# Balancer.net
KiCad netlist of a schematic drawn in EAGLE
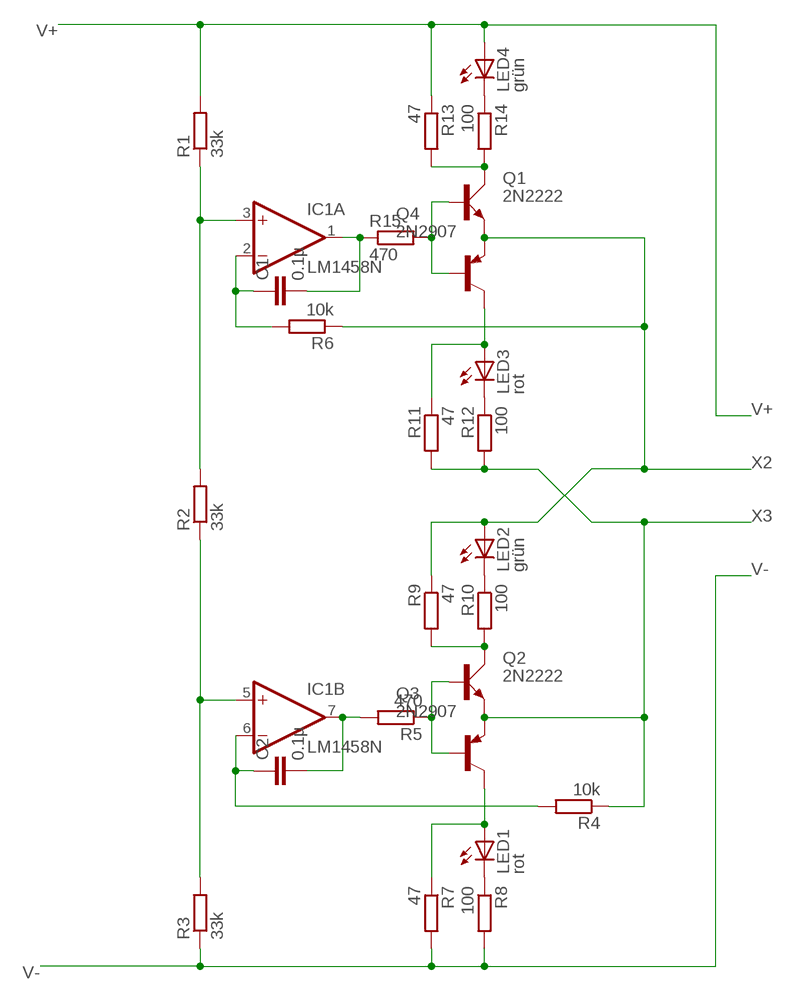
[diagram p0: schematic, sheet 1]

(export (version "E")
  (design (tool "Eeschema 10.0.6"))
  (components
    (comp (ref "C1")
      (value "0.1µ")
      (footprint "eagle-import:C050-025X075")
      (libsource (lib "eagle-import") (part "C-EU050-025X075"))
    )
    (comp (ref "C2")
      (value "0.1µ")
      (footprint "eagle-import:C050-025X075")
      (libsource (lib "eagle-import") (part "C-EU050-025X075"))
    )
    (comp (ref "IC1")
      (value "LM1458N")
      (footprint "eagle-import:DIL08")
      (libsource (lib "eagle-import") (part "1458NLM"))
    )
    (comp (ref "LED1")
      (value "rot")
      (footprint "eagle-import:LED5MM")
      (libsource (lib "eagle-import") (part "LED5MM"))
    )
    (comp (ref "LED2")
      (value "grün")
      (footprint "eagle-import:LED5MM")
      (libsource (lib "eagle-import") (part "LED5MM"))
    )
    (comp (ref "LED3")
      (value "rot")
      (footprint "eagle-import:LED5MM")
      (libsource (lib "eagle-import") (part "LED5MM"))
    )
    (comp (ref "LED4")
      (value "grün")
      (footprint "eagle-import:LED5MM")
      (libsource (lib "eagle-import") (part "LED5MM"))
    )
    (comp (ref "Q1")
      (value "2N2222")
      (footprint "eagle-import:TO18A")
      (libsource (lib "eagle-import") (part "2N2222"))
    )
    (comp (ref "Q2")
      (value "2N2222")
      (footprint "eagle-import:TO18A")
      (libsource (lib "eagle-import") (part "2N2222"))
    )
    (comp (ref "Q3")
      (value "2N2907")
      (footprint "eagle-import:TO18")
      (libsource (lib "eagle-import") (part "2N2907"))
    )
    (comp (ref "Q4")
      (value "2N2907")
      (footprint "eagle-import:TO18")
      (libsource (lib "eagle-import") (part "2N2907"))
    )
    (comp (ref "R1")
      (value "33k")
      (footprint "eagle-import:0204_5")
      (libsource (lib "eagle-import") (part "R-EU_0204/5"))
    )
    (comp (ref "R2")
      (value "33k")
      (footprint "eagle-import:0204_5")
      (libsource (lib "eagle-import") (part "R-EU_0204/5"))
    )
    (comp (ref "R3")
      (value "33k")
      (footprint "eagle-import:0204_5")
      (libsource (lib "eagle-import") (part "R-EU_0204/5"))
    )
    (comp (ref "R4")
      (value "10k")
      (footprint "eagle-import:0204_5")
      (libsource (lib "eagle-import") (part "R-EU_0204/5"))
    )
    (comp (ref "R5")
      (value "470")
      (footprint "eagle-import:0204_5")
      (libsource (lib "eagle-import") (part "R-EU_0204/5"))
    )
    (comp (ref "R6")
      (value "10k")
      (footprint "eagle-import:0204_5")
      (libsource (lib "eagle-import") (part "R-EU_0204/5"))
    )
    (comp (ref "R7")
      (value "47")
      (footprint "eagle-import:0204_5")
      (libsource (lib "eagle-import") (part "R-EU_0204/5"))
    )
    (comp (ref "R8")
      (value "100")
      (footprint "eagle-import:0204_5")
      (libsource (lib "eagle-import") (part "R-EU_0204/5"))
    )
    (comp (ref "R9")
      (value "47")
      (footprint "eagle-import:0204_5")
      (libsource (lib "eagle-import") (part "R-EU_0204/5"))
    )
    (comp (ref "R10")
      (value "100")
      (footprint "eagle-import:0204_5")
      (libsource (lib "eagle-import") (part "R-EU_0204/5"))
    )
    (comp (ref "R11")
      (value "47")
      (footprint "eagle-import:0204_5")
      (libsource (lib "eagle-import") (part "R-EU_0204/5"))
    )
    (comp (ref "R12")
      (value "100")
      (footprint "eagle-import:0204_5")
      (libsource (lib "eagle-import") (part "R-EU_0204/5"))
    )
    (comp (ref "R13")
      (value "47")
      (footprint "eagle-import:0204_5")
      (libsource (lib "eagle-import") (part "R-EU_0204/5"))
    )
    (comp (ref "R14")
      (value "100")
      (footprint "eagle-import:0204_5")
      (libsource (lib "eagle-import") (part "R-EU_0204/5"))
    )
    (comp (ref "R15")
      (value "470")
      (footprint "eagle-import:0204_5")
      (libsource (lib "eagle-import") (part "R-EU_0204/5"))
    )
  )
  (nets
    (net (code "1") (name "/V+") (class "Default")
      (node (ref "LED4") (pin "A") (pinfunction "A_A") (pintype "passive"))
      (node (ref "R1") (pin "2") (pinfunction "2_2") (pintype "passive"))
      (node (ref "R13") (pin "1") (pinfunction "1_1") (pintype "passive"))
    )
    (net (code "2") (name "/V-") (class "Default")
      (node (ref "R3") (pin "1") (pinfunction "1_1") (pintype "passive"))
      (node (ref "R7") (pin "2") (pinfunction "2_2") (pintype "passive"))
      (node (ref "R8") (pin "2") (pinfunction "2_2") (pintype "passive"))
    )
    (net (code "3") (name "/X2") (class "Default")
      (node (ref "LED2") (pin "A") (pinfunction "A_A") (pintype "passive"))
      (node (ref "Q1") (pin "E") (pinfunction "E_E") (pintype "passive"))
      (node (ref "Q4") (pin "1") (pinfunction "E_1") (pintype "passive"))
      (node (ref "R6") (pin "1") (pinfunction "1_1") (pintype "passive"))
      (node (ref "R9") (pin "1") (pinfunction "1_1") (pintype "passive"))
    )
    (net (code "4") (name "/X3") (class "Default")
      (node (ref "Q2") (pin "E") (pinfunction "E_E") (pintype "passive"))
      (node (ref "Q3") (pin "1") (pinfunction "E_1") (pintype "passive"))
      (node (ref "R11") (pin "2") (pinfunction "2_2") (pintype "passive"))
      (node (ref "R12") (pin "2") (pinfunction "2_2") (pintype "passive"))
      (node (ref "R4") (pin "1") (pinfunction "1_1") (pintype "passive"))
    )
    (net (code "5") (name "Net-(IC1A-+IN)") (class "Default")
      (node (ref "IC1") (pin "3") (pinfunction "+IN_3") (pintype "input"))
      (node (ref "R1") (pin "1") (pinfunction "1_1") (pintype "passive"))
      (node (ref "R2") (pin "2") (pinfunction "2_2") (pintype "passive"))
    )
    (net (code "6") (name "Net-(IC1A--IN)") (class "Default")
      (node (ref "C1") (pin "1") (pinfunction "1_1") (pintype "passive"))
      (node (ref "IC1") (pin "2") (pinfunction "-IN_2") (pintype "input"))
      (node (ref "R6") (pin "2") (pinfunction "2_2") (pintype "passive"))
    )
    (net (code "7") (name "Net-(IC1A-OUT)") (class "Default")
      (node (ref "C1") (pin "2") (pinfunction "2_2") (pintype "passive"))
      (node (ref "IC1") (pin "1") (pinfunction "OUT_1") (pintype "output"))
      (node (ref "R15") (pin "1") (pinfunction "1_1") (pintype "passive"))
    )
    (net (code "8") (name "Net-(IC1B-+IN)") (class "Default")
      (node (ref "IC1") (pin "5") (pinfunction "+IN_5") (pintype "input"))
      (node (ref "R2") (pin "1") (pinfunction "1_1") (pintype "passive"))
      (node (ref "R3") (pin "2") (pinfunction "2_2") (pintype "passive"))
    )
    (net (code "9") (name "Net-(IC1B--IN)") (class "Default")
      (node (ref "C2") (pin "1") (pinfunction "1_1") (pintype "passive"))
      (node (ref "IC1") (pin "6") (pinfunction "-IN_6") (pintype "input"))
      (node (ref "R4") (pin "2") (pinfunction "2_2") (pintype "passive"))
    )
    (net (code "10") (name "Net-(IC1B-OUT)") (class "Default")
      (node (ref "C2") (pin "2") (pinfunction "2_2") (pintype "passive"))
      (node (ref "IC1") (pin "7") (pinfunction "OUT_7") (pintype "output"))
      (node (ref "R5") (pin "2") (pinfunction "2_2") (pintype "passive"))
    )
    (net (code "11") (name "Net-(LED1-C)") (class "Default")
      (node (ref "LED1") (pin "K") (pinfunction "C_K") (pintype "passive"))
      (node (ref "R8") (pin "1") (pinfunction "1_1") (pintype "passive"))
    )
    (net (code "12") (name "Net-(LED2-C)") (class "Default")
      (node (ref "LED2") (pin "K") (pinfunction "C_K") (pintype "passive"))
      (node (ref "R10") (pin "1") (pinfunction "1_1") (pintype "passive"))
    )
    (net (code "13") (name "Net-(LED3-C)") (class "Default")
      (node (ref "LED3") (pin "K") (pinfunction "C_K") (pintype "passive"))
      (node (ref "R12") (pin "1") (pinfunction "1_1") (pintype "passive"))
    )
    (net (code "14") (name "Net-(LED4-C)") (class "Default")
      (node (ref "LED4") (pin "K") (pinfunction "C_K") (pintype "passive"))
      (node (ref "R14") (pin "1") (pinfunction "1_1") (pintype "passive"))
    )
    (net (code "15") (name "Net-(Q1-PadC)") (class "Default")
      (node (ref "Q1") (pin "C") (pinfunction "C_C") (pintype "passive"))
      (node (ref "R13") (pin "2") (pinfunction "2_2") (pintype "passive"))
      (node (ref "R14") (pin "2") (pinfunction "2_2") (pintype "passive"))
    )
    (net (code "16") (name "Net-(Q2-PadC)") (class "Default")
      (node (ref "Q2") (pin "C") (pinfunction "C_C") (pintype "passive"))
      (node (ref "R10") (pin "2") (pinfunction "2_2") (pintype "passive"))
      (node (ref "R9") (pin "2") (pinfunction "2_2") (pintype "passive"))
    )
    (net (code "17") (name "Net-(Q3-B)") (class "Default")
      (node (ref "Q2") (pin "B") (pinfunction "B_B") (pintype "passive"))
      (node (ref "Q3") (pin "2") (pinfunction "B_2") (pintype "passive"))
      (node (ref "R5") (pin "1") (pinfunction "1_1") (pintype "passive"))
    )
    (net (code "18") (name "Net-(Q3-C)") (class "Default")
      (node (ref "LED1") (pin "A") (pinfunction "A_A") (pintype "passive"))
      (node (ref "Q3") (pin "3") (pinfunction "C_3") (pintype "passive"))
      (node (ref "R7") (pin "1") (pinfunction "1_1") (pintype "passive"))
    )
    (net (code "19") (name "Net-(Q4-B)") (class "Default")
      (node (ref "Q1") (pin "B") (pinfunction "B_B") (pintype "passive"))
      (node (ref "Q4") (pin "2") (pinfunction "B_2") (pintype "passive"))
      (node (ref "R15") (pin "2") (pinfunction "2_2") (pintype "passive"))
    )
    (net (code "20") (name "Net-(Q4-C)") (class "Default")
      (node (ref "LED3") (pin "A") (pinfunction "A_A") (pintype "passive"))
      (node (ref "Q4") (pin "3") (pinfunction "C_3") (pintype "passive"))
      (node (ref "R11") (pin "1") (pinfunction "1_1") (pintype "passive"))
    )
  )
)
